# SCH_CustomESP32Board_2024-06-23.net
KiCad netlist of a schematic drawn in EasyEDA
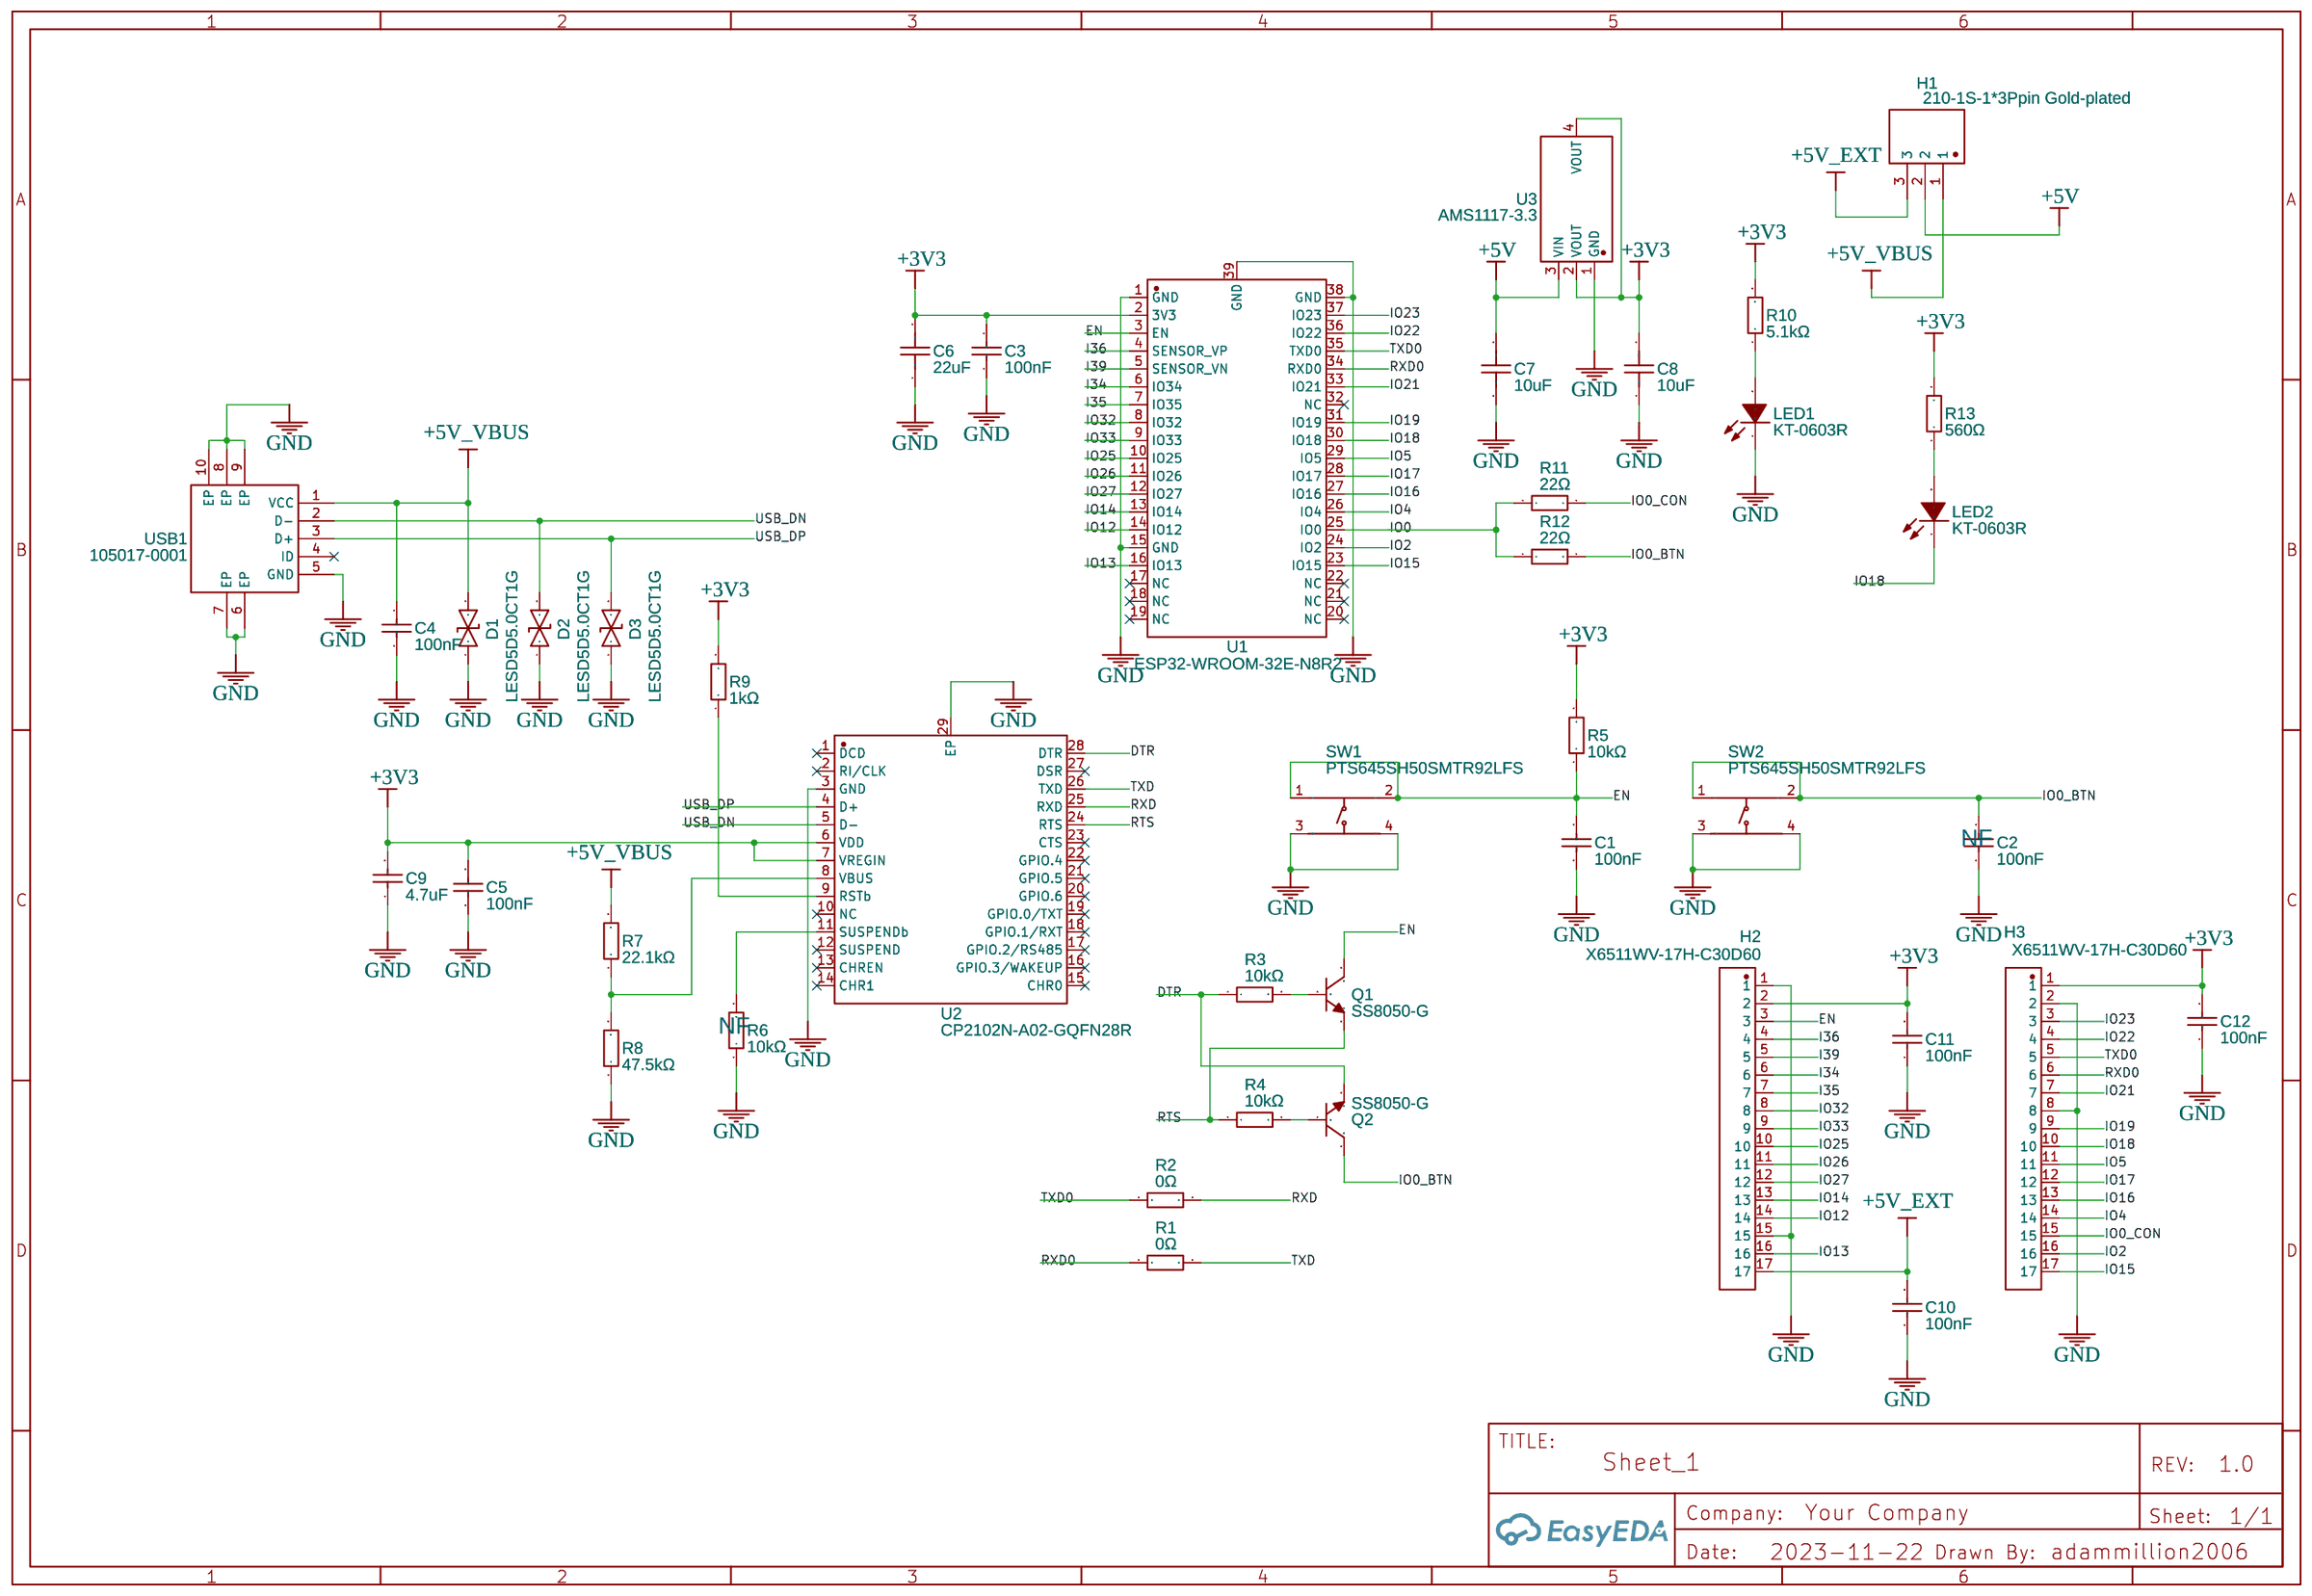
[diagram p0: schematic sheet]

(export (version "E")
  (design (tool "Eeschema 10.0.6"))
  (components
    (comp (ref "C1")
      (value "100nF")
      (fields
        (field (name "Manufacturer Part") "CL05B104KO5NNNC")
        (field (name "Manufacturer") "SAMSUNG(三星)")
      )
      (libsource (lib "") (part "CL05B104KO5NNNC"))
    )
    (comp (ref "C2")
      (value "100nF")
      (fields
        (field (name "Manufacturer Part") "CL05B104KO5NNNC")
        (field (name "Manufacturer") "SAMSUNG(三星)")
      )
      (libsource (lib "") (part "CL05B104KO5NNNC"))
    )
    (comp (ref "C3")
      (value "100nF")
      (fields
        (field (name "Manufacturer Part") "CL05B104KO5NNNC")
        (field (name "Manufacturer") "SAMSUNG(三星)")
      )
      (libsource (lib "") (part "CL05B104KO5NNNC"))
    )
    (comp (ref "C4")
      (value "100nF")
      (fields
        (field (name "Manufacturer Part") "CL05B104KO5NNNC")
        (field (name "Manufacturer") "SAMSUNG(三星)")
      )
      (libsource (lib "") (part "CL05B104KO5NNNC"))
    )
    (comp (ref "C5")
      (value "100nF")
      (fields
        (field (name "Manufacturer Part") "CL05B104KO5NNNC")
        (field (name "Manufacturer") "SAMSUNG(三星)")
      )
      (libsource (lib "") (part "CL05B104KO5NNNC"))
    )
    (comp (ref "C6")
      (value "22uF")
      (fields
        (field (name "Manufacturer Part") "CL21A226MAQNNNE")
        (field (name "Manufacturer") "SAMSUNG(三星)")
      )
      (libsource (lib "") (part "CL21A226MAQNNNE"))
    )
    (comp (ref "C7")
      (value "10uF")
      (fields
        (field (name "Manufacturer Part") "CL10A106KP8NNNC")
        (field (name "Manufacturer") "SAMSUNG(三星)")
      )
      (libsource (lib "") (part "CL10A106KP8NNNC"))
    )
    (comp (ref "C8")
      (value "10uF")
      (fields
        (field (name "Manufacturer Part") "CL10A106KP8NNNC")
        (field (name "Manufacturer") "SAMSUNG(三星)")
      )
      (libsource (lib "") (part "CL10A106KP8NNNC"))
    )
    (comp (ref "C9")
      (value "4.7uF")
      (fields
        (field (name "Manufacturer Part") "CL05A475MP5NRNC")
        (field (name "Manufacturer") "SAMSUNG(三星)")
      )
      (libsource (lib "") (part "CL05A475MP5NRNC"))
    )
    (comp (ref "C10")
      (value "100nF")
      (fields
        (field (name "Manufacturer Part") "CL05B104KO5NNNC")
        (field (name "Manufacturer") "SAMSUNG(三星)")
      )
      (libsource (lib "") (part "CL05B104KO5NNNC"))
    )
    (comp (ref "C11")
      (value "100nF")
      (fields
        (field (name "Manufacturer Part") "CL05B104KO5NNNC")
        (field (name "Manufacturer") "SAMSUNG(三星)")
      )
      (libsource (lib "") (part "CL05B104KO5NNNC"))
    )
    (comp (ref "C12")
      (value "100nF")
      (fields
        (field (name "Manufacturer Part") "CL05B104KO5NNNC")
        (field (name "Manufacturer") "SAMSUNG(三星)")
      )
      (libsource (lib "") (part "CL05B104KO5NNNC"))
    )
    (comp (ref "D1")
      (value "LESD5D5.0CT1G")
      (fields (field (name "Manufacturer") "LRC(乐山无线电)"))
      (libsource (lib "") (part "LESD5D5.0CT1G"))
    )
    (comp (ref "D2")
      (value "LESD5D5.0CT1G")
      (fields (field (name "Manufacturer") "LRC(乐山无线电)"))
      (libsource (lib "") (part "LESD5D5.0CT1G"))
    )
    (comp (ref "D3")
      (value "LESD5D5.0CT1G")
      (fields (field (name "Manufacturer") "LRC(乐山无线电)"))
      (libsource (lib "") (part "LESD5D5.0CT1G"))
    )
    (comp (ref "H1")
      (value "210-1S-1*3Ppin Gold-plated")
      (fields (field (name "Manufacturer Part") "B-2101S03P-A110") (field (name "Manufacturer") "Ckmtw(灿科盟)"))
      (libsource (lib "") (part "210-1S-1*3Ppin Gold-plated"))
    )
    (comp (ref "H2")
      (value "X6511WV-17H-C30D60")
      (fields
        (field (name "Manufacturer Part") "X6511WV-17H-C60D30")
        (field (name "Manufacturer") "XKB Connectivity(中国星坤)")
      )
      (libsource (lib "") (part "X6511WV-17H-C30D60"))
    )
    (comp (ref "H3")
      (value "X6511WV-17H-C30D60")
      (fields
        (field (name "Manufacturer Part") "X6511WV-17H-C60D30")
        (field (name "Manufacturer") "XKB Connectivity(中国星坤)")
      )
      (libsource (lib "") (part "X6511WV-17H-C30D60"))
    )
    (comp (ref "LED1")
      (value "KT-0603R")
      (fields (field (name "Manufacturer") "KENTO"))
      (libsource (lib "") (part "KT-0603R"))
    )
    (comp (ref "LED2")
      (value "KT-0603R")
      (fields (field (name "Manufacturer") "KENTO"))
      (libsource (lib "") (part "KT-0603R"))
    )
    (comp (ref "Q1")
      (value "SS8050-G")
      (fields (field (name "Manufacturer") "CJ(江苏长电/长晶)"))
      (libsource (lib "") (part "SS8050-G_1"))
    )
    (comp (ref "Q2")
      (value "SS8050-G")
      (fields (field (name "Manufacturer") "CJ(江苏长电/长晶)"))
      (libsource (lib "") (part "SS8050-G"))
    )
    (comp (ref "R1")
      (value "0Ω")
      (fields
        (field (name "Manufacturer Part") "0402WGF0000TCE")
        (field (name "Manufacturer") "UNI-ROYAL(厚声)")
      )
      (libsource (lib "") (part "0402WGF0000TCE"))
    )
    (comp (ref "R2")
      (value "0Ω")
      (fields
        (field (name "Manufacturer Part") "0402WGF0000TCE")
        (field (name "Manufacturer") "UNI-ROYAL(厚声)")
      )
      (libsource (lib "") (part "0402WGF0000TCE"))
    )
    (comp (ref "R3")
      (value "10kΩ")
      (fields
        (field (name "Manufacturer Part") "0402WGF1002TCE")
        (field (name "Manufacturer") "UNI-ROYAL(厚声)")
      )
      (libsource (lib "") (part "0402WGF1002TCE_1"))
    )
    (comp (ref "R4")
      (value "10kΩ")
      (fields
        (field (name "Manufacturer Part") "0402WGF1002TCE")
        (field (name "Manufacturer") "UNI-ROYAL(厚声)")
      )
      (libsource (lib "") (part "0402WGF1002TCE_1"))
    )
    (comp (ref "R5")
      (value "10kΩ")
      (fields
        (field (name "Manufacturer Part") "0402WGF1002TCE")
        (field (name "Manufacturer") "UNI-ROYAL(厚声)")
      )
      (libsource (lib "") (part "0402WGF1002TCE"))
    )
    (comp (ref "R6")
      (value "10kΩ")
      (fields
        (field (name "Manufacturer Part") "0402WGF1002TCE")
        (field (name "Manufacturer") "UNI-ROYAL(厚声)")
      )
      (libsource (lib "") (part "0402WGF1002TCE"))
    )
    (comp (ref "R7")
      (value "22.1kΩ")
      (fields
        (field (name "Manufacturer Part") "0402WGF2212TCE")
        (field (name "Manufacturer") "UNI-ROYAL(厚声)")
      )
      (libsource (lib "") (part "0402WGF2212TCE"))
    )
    (comp (ref "R8")
      (value "47.5kΩ")
      (fields
        (field (name "Manufacturer Part") "0402WGF4752TCE")
        (field (name "Manufacturer") "UNI-ROYAL(厚声)")
      )
      (libsource (lib "") (part "0402WGF4752TCE"))
    )
    (comp (ref "R9")
      (value "1kΩ")
      (fields
        (field (name "Manufacturer Part") "0402WGF1001TCE")
        (field (name "Manufacturer") "UNI-ROYAL(厚声)")
      )
      (libsource (lib "") (part "0402WGF1001TCE"))
    )
    (comp (ref "R10")
      (value "5.1kΩ")
      (fields
        (field (name "Manufacturer Part") "0402WGF5101TCE")
        (field (name "Manufacturer") "UNI-ROYAL(厚声)")
      )
      (libsource (lib "") (part "0402WGF5101TCE"))
    )
    (comp (ref "R11")
      (value "22Ω")
      (fields
        (field (name "Manufacturer Part") "0402WGF220JTCE")
        (field (name "Manufacturer") "UNI-ROYAL(厚声)")
      )
      (libsource (lib "") (part "0402WGF220JTCE"))
    )
    (comp (ref "R12")
      (value "22Ω")
      (fields
        (field (name "Manufacturer Part") "0402WGF220JTCE")
        (field (name "Manufacturer") "UNI-ROYAL(厚声)")
      )
      (libsource (lib "") (part "0402WGF220JTCE"))
    )
    (comp (ref "R13")
      (value "560Ω")
      (fields
        (field (name "Manufacturer Part") "0402WGF5600TCE")
        (field (name "Manufacturer") "UNI-ROYAL(厚声)")
      )
      (libsource (lib "") (part "0402WGF5600TCE"))
    )
    (comp (ref "SW1")
      (value "PTS645SH50SMTR92LFS")
      (fields (field (name "Manufacturer") "C&K"))
      (libsource (lib "") (part "PTS645SH50SMTR92LFS"))
    )
    (comp (ref "SW2")
      (value "PTS645SH50SMTR92LFS")
      (fields (field (name "Manufacturer") "C&K"))
      (libsource (lib "") (part "PTS645SH50SMTR92LFS"))
    )
    (comp (ref "U1")
      (value "ESP32-WROOM-32E-N8R2")
      (fields (field (name "Manufacturer") "ESPRESSIF(乐鑫)"))
      (libsource (lib "") (part "ESP32-WROOM-32E-N8R2"))
    )
    (comp (ref "U2")
      (value "CP2102N-A02-GQFN28R")
      (fields (field (name "Manufacturer") "SILICON LABS(芯科)"))
      (libsource (lib "") (part "CP2102N-A02-GQFN28R"))
    )
    (comp (ref "U3")
      (value "AMS1117-3.3")
      (fields (field (name "Manufacturer") "AMS"))
      (libsource (lib "") (part "AMS1117-3.3"))
    )
    (comp (ref "USB1")
      (value "105017-0001")
      (fields (field (name "Manufacturer Part") "1050170001") (field (name "Manufacturer") "MOLEX"))
      (libsource (lib "") (part "105017-0001"))
    )
  )
  (nets
    (net (code "1") (name "+3V3") (class "Default")
      (node (ref "C11") (pin "2") (pinfunction "2_2") (pintype "input"))
      (node (ref "C12") (pin "2") (pinfunction "2_2") (pintype "input"))
      (node (ref "C3") (pin "2") (pinfunction "2_2") (pintype "input"))
      (node (ref "C5") (pin "2") (pinfunction "2_2") (pintype "input"))
      (node (ref "C6") (pin "2") (pinfunction "2_2") (pintype "unspecified"))
      (node (ref "C8") (pin "2") (pinfunction "2_2") (pintype "unspecified"))
      (node (ref "C9") (pin "2") (pinfunction "2_2") (pintype "input"))
      (node (ref "H2") (pin "2") (pinfunction "2_2") (pintype "unspecified"))
      (node (ref "H3") (pin "1") (pinfunction "1_1") (pintype "unspecified"))
      (node (ref "R10") (pin "2") (pinfunction "2_2") (pintype "input"))
      (node (ref "R13") (pin "2") (pinfunction "2_2") (pintype "input"))
      (node (ref "R5") (pin "2") (pinfunction "2_2") (pintype "input"))
      (node (ref "R9") (pin "2") (pinfunction "2_2") (pintype "input"))
      (node (ref "U1") (pin "2") (pinfunction "3V3_2") (pintype "unspecified"))
      (node (ref "U2") (pin "6") (pinfunction "VDD_6") (pintype "unspecified"))
      (node (ref "U2") (pin "7") (pinfunction "VREGIN_7") (pintype "unspecified"))
      (node (ref "U3") (pin "2") (pinfunction "VOUT_2") (pintype "unspecified"))
      (node (ref "U3") (pin "4") (pinfunction "VOUT_4") (pintype "unspecified"))
    )
    (net (code "2") (name "+5V") (class "Default")
      (node (ref "C7") (pin "2") (pinfunction "2_2") (pintype "unspecified"))
      (node (ref "H1") (pin "2") (pinfunction "2_2") (pintype "unspecified"))
      (node (ref "U3") (pin "3") (pinfunction "VIN_3") (pintype "unspecified"))
    )
    (net (code "3") (name "+5V_EXT") (class "Default")
      (node (ref "C10") (pin "2") (pinfunction "2_2") (pintype "input"))
      (node (ref "H1") (pin "3") (pinfunction "3_3") (pintype "unspecified"))
      (node (ref "H2") (pin "17") (pinfunction "17_17") (pintype "unspecified"))
    )
    (net (code "4") (name "+5V_VBUS") (class "Default")
      (node (ref "C4") (pin "2") (pinfunction "2_2") (pintype "input"))
      (node (ref "D1") (pin "2") (pinfunction "2_2") (pintype "unspecified"))
      (node (ref "H1") (pin "1") (pinfunction "1_1") (pintype "unspecified"))
      (node (ref "R7") (pin "2") (pinfunction "2_2") (pintype "input"))
      (node (ref "USB1") (pin "1") (pinfunction "VCC_1") (pintype "unspecified"))
    )
    (net (code "5") (name "/DTR") (class "Default")
      (node (ref "Q2") (pin "2") (pinfunction "E_2") (pintype "input"))
      (node (ref "R3") (pin "1") (pinfunction "1_1") (pintype "input"))
      (node (ref "U2") (pin "28") (pinfunction "DTR_28") (pintype "unspecified"))
    )
    (net (code "6") (name "/EN") (class "Default")
      (node (ref "C1") (pin "2") (pinfunction "2_2") (pintype "input"))
      (node (ref "H2") (pin "3") (pinfunction "3_3") (pintype "unspecified"))
      (node (ref "Q1") (pin "3") (pinfunction "C_3") (pintype "input"))
      (node (ref "R5") (pin "1") (pinfunction "1_1") (pintype "input"))
      (node (ref "SW1") (pin "1") (pinfunction "1_1") (pintype "unspecified"))
      (node (ref "SW1") (pin "2") (pinfunction "2_2") (pintype "unspecified"))
      (node (ref "U1") (pin "3") (pinfunction "EN_3") (pintype "unspecified"))
    )
    (net (code "7") (name "/I34") (class "Default")
      (node (ref "H2") (pin "6") (pinfunction "6_6") (pintype "unspecified"))
      (node (ref "U1") (pin "6") (pinfunction "IO34_6") (pintype "unspecified"))
    )
    (net (code "8") (name "/I35") (class "Default")
      (node (ref "H2") (pin "7") (pinfunction "7_7") (pintype "unspecified"))
      (node (ref "U1") (pin "7") (pinfunction "IO35_7") (pintype "unspecified"))
    )
    (net (code "9") (name "/I36") (class "Default")
      (node (ref "H2") (pin "4") (pinfunction "4_4") (pintype "unspecified"))
      (node (ref "U1") (pin "4") (pinfunction "SENSOR_VP_4") (pintype "unspecified"))
    )
    (net (code "10") (name "/I39") (class "Default")
      (node (ref "H2") (pin "5") (pinfunction "5_5") (pintype "unspecified"))
      (node (ref "U1") (pin "5") (pinfunction "SENSOR_VN_5") (pintype "unspecified"))
    )
    (net (code "11") (name "/IO0") (class "Default")
      (node (ref "R11") (pin "1") (pinfunction "1_1") (pintype "input"))
      (node (ref "R12") (pin "1") (pinfunction "1_1") (pintype "input"))
      (node (ref "U1") (pin "25") (pinfunction "IO0_25") (pintype "unspecified"))
    )
    (net (code "12") (name "/IO0_BTN") (class "Default")
      (node (ref "C2") (pin "2") (pinfunction "2_2") (pintype "input"))
      (node (ref "Q2") (pin "3") (pinfunction "C_3") (pintype "input"))
      (node (ref "R12") (pin "2") (pinfunction "2_2") (pintype "input"))
      (node (ref "SW2") (pin "1") (pinfunction "1_1") (pintype "unspecified"))
      (node (ref "SW2") (pin "2") (pinfunction "2_2") (pintype "unspecified"))
    )
    (net (code "13") (name "/IO0_CON") (class "Default")
      (node (ref "H3") (pin "15") (pinfunction "15_15") (pintype "unspecified"))
      (node (ref "R11") (pin "2") (pinfunction "2_2") (pintype "input"))
    )
    (net (code "14") (name "/IO2") (class "Default")
      (node (ref "H3") (pin "16") (pinfunction "16_16") (pintype "unspecified"))
      (node (ref "U1") (pin "24") (pinfunction "IO2_24") (pintype "unspecified"))
    )
    (net (code "15") (name "/IO4") (class "Default")
      (node (ref "H3") (pin "14") (pinfunction "14_14") (pintype "unspecified"))
      (node (ref "U1") (pin "26") (pinfunction "IO4_26") (pintype "unspecified"))
    )
    (net (code "16") (name "/IO5") (class "Default")
      (node (ref "H3") (pin "11") (pinfunction "11_11") (pintype "unspecified"))
      (node (ref "U1") (pin "29") (pinfunction "IO5_29") (pintype "unspecified"))
    )
    (net (code "17") (name "/IO12") (class "Default")
      (node (ref "H2") (pin "14") (pinfunction "14_14") (pintype "unspecified"))
      (node (ref "U1") (pin "14") (pinfunction "IO12_14") (pintype "unspecified"))
    )
    (net (code "18") (name "/IO13") (class "Default")
      (node (ref "H2") (pin "16") (pinfunction "16_16") (pintype "unspecified"))
      (node (ref "U1") (pin "16") (pinfunction "IO13_16") (pintype "unspecified"))
    )
    (net (code "19") (name "/IO14") (class "Default")
      (node (ref "H2") (pin "13") (pinfunction "13_13") (pintype "unspecified"))
      (node (ref "U1") (pin "13") (pinfunction "IO14_13") (pintype "unspecified"))
    )
    (net (code "20") (name "/IO15") (class "Default")
      (node (ref "H3") (pin "17") (pinfunction "17_17") (pintype "unspecified"))
      (node (ref "U1") (pin "23") (pinfunction "IO15_23") (pintype "unspecified"))
    )
    (net (code "21") (name "/IO16") (class "Default")
      (node (ref "H3") (pin "13") (pinfunction "13_13") (pintype "unspecified"))
      (node (ref "U1") (pin "27") (pinfunction "IO16_27") (pintype "unspecified"))
    )
    (net (code "22") (name "/IO17") (class "Default")
      (node (ref "H3") (pin "12") (pinfunction "12_12") (pintype "unspecified"))
      (node (ref "U1") (pin "28") (pinfunction "IO17_28") (pintype "unspecified"))
    )
    (net (code "23") (name "/IO18") (class "Default")
      (node (ref "H3") (pin "10") (pinfunction "10_10") (pintype "unspecified"))
      (node (ref "LED2") (pin "1") (pinfunction "K_1") (pintype "unspecified"))
      (node (ref "U1") (pin "30") (pinfunction "IO18_30") (pintype "unspecified"))
    )
    (net (code "24") (name "/IO19") (class "Default")
      (node (ref "H3") (pin "9") (pinfunction "9_9") (pintype "unspecified"))
      (node (ref "U1") (pin "31") (pinfunction "IO19_31") (pintype "unspecified"))
    )
    (net (code "25") (name "/IO21") (class "Default")
      (node (ref "H3") (pin "7") (pinfunction "7_7") (pintype "unspecified"))
      (node (ref "U1") (pin "33") (pinfunction "IO21_33") (pintype "unspecified"))
    )
    (net (code "26") (name "/IO22") (class "Default")
      (node (ref "H3") (pin "4") (pinfunction "4_4") (pintype "unspecified"))
      (node (ref "U1") (pin "36") (pinfunction "IO22_36") (pintype "unspecified"))
    )
    (net (code "27") (name "/IO23") (class "Default")
      (node (ref "H3") (pin "3") (pinfunction "3_3") (pintype "unspecified"))
      (node (ref "U1") (pin "37") (pinfunction "IO23_37") (pintype "unspecified"))
    )
    (net (code "28") (name "/IO25") (class "Default")
      (node (ref "H2") (pin "10") (pinfunction "10_10") (pintype "unspecified"))
      (node (ref "U1") (pin "10") (pinfunction "IO25_10") (pintype "unspecified"))
    )
    (net (code "29") (name "/IO26") (class "Default")
      (node (ref "H2") (pin "11") (pinfunction "11_11") (pintype "unspecified"))
      (node (ref "U1") (pin "11") (pinfunction "IO26_11") (pintype "unspecified"))
    )
    (net (code "30") (name "/IO27") (class "Default")
      (node (ref "H2") (pin "12") (pinfunction "12_12") (pintype "unspecified"))
      (node (ref "U1") (pin "12") (pinfunction "IO27_12") (pintype "unspecified"))
    )
    (net (code "31") (name "/IO32") (class "Default")
      (node (ref "H2") (pin "8") (pinfunction "8_8") (pintype "unspecified"))
      (node (ref "U1") (pin "8") (pinfunction "IO32_8") (pintype "unspecified"))
    )
    (net (code "32") (name "/IO33") (class "Default")
      (node (ref "H2") (pin "9") (pinfunction "9_9") (pintype "unspecified"))
      (node (ref "U1") (pin "9") (pinfunction "IO33_9") (pintype "unspecified"))
    )
    (net (code "33") (name "/RTS") (class "Default")
      (node (ref "Q1") (pin "2") (pinfunction "E_2") (pintype "input"))
      (node (ref "R4") (pin "1") (pinfunction "1_1") (pintype "input"))
      (node (ref "U2") (pin "24") (pinfunction "RTS_24") (pintype "unspecified"))
    )
    (net (code "34") (name "/RXD") (class "Default")
      (node (ref "R2") (pin "2") (pinfunction "2_2") (pintype "input"))
      (node (ref "U2") (pin "25") (pinfunction "RXD_25") (pintype "unspecified"))
    )
    (net (code "35") (name "/RXD0") (class "Default")
      (node (ref "H3") (pin "6") (pinfunction "6_6") (pintype "unspecified"))
      (node (ref "R1") (pin "1") (pinfunction "1_1") (pintype "input"))
      (node (ref "U1") (pin "34") (pinfunction "RXD0_34") (pintype "unspecified"))
    )
    (net (code "36") (name "/TXD") (class "Default")
      (node (ref "R1") (pin "2") (pinfunction "2_2") (pintype "input"))
      (node (ref "U2") (pin "26") (pinfunction "TXD_26") (pintype "unspecified"))
    )
    (net (code "37") (name "/TXD0") (class "Default")
      (node (ref "H3") (pin "5") (pinfunction "5_5") (pintype "unspecified"))
      (node (ref "R2") (pin "1") (pinfunction "1_1") (pintype "input"))
      (node (ref "U1") (pin "35") (pinfunction "TXD0_35") (pintype "unspecified"))
    )
    (net (code "38") (name "/USB_DN") (class "Default")
      (node (ref "D2") (pin "2") (pinfunction "2_2") (pintype "unspecified"))
      (node (ref "U2") (pin "5") (pinfunction "D-_5") (pintype "unspecified"))
      (node (ref "USB1") (pin "2") (pinfunction "D-_2") (pintype "unspecified"))
    )
    (net (code "39") (name "/USB_DP") (class "Default")
      (node (ref "D3") (pin "2") (pinfunction "2_2") (pintype "unspecified"))
      (node (ref "U2") (pin "4") (pinfunction "D+_4") (pintype "unspecified"))
      (node (ref "USB1") (pin "3") (pinfunction "D+_3") (pintype "unspecified"))
    )
    (net (code "40") (name "GND") (class "Default")
      (node (ref "C1") (pin "1") (pinfunction "1_1") (pintype "input"))
      (node (ref "C10") (pin "1") (pinfunction "1_1") (pintype "input"))
      (node (ref "C11") (pin "1") (pinfunction "1_1") (pintype "input"))
      (node (ref "C12") (pin "1") (pinfunction "1_1") (pintype "input"))
      (node (ref "C2") (pin "1") (pinfunction "1_1") (pintype "input"))
      (node (ref "C3") (pin "1") (pinfunction "1_1") (pintype "input"))
      (node (ref "C4") (pin "1") (pinfunction "1_1") (pintype "input"))
      (node (ref "C5") (pin "1") (pinfunction "1_1") (pintype "input"))
      (node (ref "C6") (pin "1") (pinfunction "1_1") (pintype "unspecified"))
      (node (ref "C7") (pin "1") (pinfunction "1_1") (pintype "unspecified"))
      (node (ref "C8") (pin "1") (pinfunction "1_1") (pintype "unspecified"))
      (node (ref "C9") (pin "1") (pinfunction "1_1") (pintype "input"))
      (node (ref "D1") (pin "1") (pinfunction "1_1") (pintype "unspecified"))
      (node (ref "D2") (pin "1") (pinfunction "1_1") (pintype "unspecified"))
      (node (ref "D3") (pin "1") (pinfunction "1_1") (pintype "unspecified"))
      (node (ref "H2") (pin "1") (pinfunction "1_1") (pintype "unspecified"))
      (node (ref "H2") (pin "15") (pinfunction "15_15") (pintype "unspecified"))
      (node (ref "H3") (pin "2") (pinfunction "2_2") (pintype "unspecified"))
      (node (ref "H3") (pin "8") (pinfunction "8_8") (pintype "unspecified"))
      (node (ref "LED1") (pin "1") (pinfunction "K_1") (pintype "unspecified"))
      (node (ref "R6") (pin "1") (pinfunction "1_1") (pintype "input"))
      (node (ref "R8") (pin "1") (pinfunction "1_1") (pintype "input"))
      (node (ref "SW1") (pin "3") (pinfunction "3_3") (pintype "unspecified"))
      (node (ref "SW1") (pin "4") (pinfunction "4_4") (pintype "unspecified"))
      (node (ref "SW2") (pin "3") (pinfunction "3_3") (pintype "unspecified"))
      (node (ref "SW2") (pin "4") (pinfunction "4_4") (pintype "unspecified"))
      (node (ref "U1") (pin "1") (pinfunction "GND_1") (pintype "unspecified"))
      (node (ref "U1") (pin "15") (pinfunction "GND_15") (pintype "unspecified"))
      (node (ref "U1") (pin "38") (pinfunction "GND_38") (pintype "unspecified"))
      (node (ref "U1") (pin "39") (pinfunction "GND_39") (pintype "unspecified"))
      (node (ref "U2") (pin "29") (pinfunction "EP_29") (pintype "unspecified"))
      (node (ref "U2") (pin "3") (pinfunction "GND_3") (pintype "unspecified"))
      (node (ref "U3") (pin "1") (pinfunction "GND_1") (pintype "unspecified"))
      (node (ref "USB1") (pin "10") (pinfunction "EP_10") (pintype "unspecified"))
      (node (ref "USB1") (pin "5") (pinfunction "GND_5") (pintype "unspecified"))
      (node (ref "USB1") (pin "6") (pinfunction "EP_6") (pintype "unspecified"))
      (node (ref "USB1") (pin "7") (pinfunction "EP_7") (pintype "unspecified"))
      (node (ref "USB1") (pin "8") (pinfunction "EP_8") (pintype "unspecified"))
      (node (ref "USB1") (pin "9") (pinfunction "EP_9") (pintype "unspecified"))
    )
    (net (code "41") (name "Net-(LED1-A)") (class "Default")
      (node (ref "LED1") (pin "2") (pinfunction "A_2") (pintype "unspecified"))
      (node (ref "R10") (pin "1") (pinfunction "1_1") (pintype "input"))
    )
    (net (code "42") (name "Net-(LED2-A)") (class "Default")
      (node (ref "LED2") (pin "2") (pinfunction "A_2") (pintype "unspecified"))
      (node (ref "R13") (pin "1") (pinfunction "1_1") (pintype "input"))
    )
    (net (code "43") (name "Net-(Q1-B)") (class "Default")
      (node (ref "Q1") (pin "1") (pinfunction "B_1") (pintype "input"))
      (node (ref "R3") (pin "2") (pinfunction "2_2") (pintype "input"))
    )
    (net (code "44") (name "Net-(Q2-B)") (class "Default")
      (node (ref "Q2") (pin "1") (pinfunction "B_1") (pintype "input"))
      (node (ref "R4") (pin "2") (pinfunction "2_2") (pintype "input"))
    )
    (net (code "45") (name "Net-(U2-RSTb)") (class "Default")
      (node (ref "R9") (pin "1") (pinfunction "1_1") (pintype "input"))
      (node (ref "U2") (pin "9") (pinfunction "RSTb_9") (pintype "unspecified"))
    )
    (net (code "46") (name "Net-(U2-SUSPENDb)") (class "Default")
      (node (ref "R6") (pin "2") (pinfunction "2_2") (pintype "input"))
      (node (ref "U2") (pin "11") (pinfunction "SUSPENDb_11") (pintype "unspecified"))
    )
    (net (code "47") (name "Net-(U2-VBUS)") (class "Default")
      (node (ref "R7") (pin "1") (pinfunction "1_1") (pintype "input"))
      (node (ref "R8") (pin "2") (pinfunction "2_2") (pintype "input"))
      (node (ref "U2") (pin "8") (pinfunction "VBUS_8") (pintype "unspecified"))
    )
    (net (code "48") (name "unconnected-(U1-NC-Pad17)") (class "Default")
      (node (ref "U1") (pin "17") (pinfunction "NC_17") (pintype "unspecified+no_connect"))
    )
    (net (code "49") (name "unconnected-(U1-NC-Pad18)") (class "Default")
      (node (ref "U1") (pin "18") (pinfunction "NC_18") (pintype "unspecified+no_connect"))
    )
    (net (code "50") (name "unconnected-(U1-NC-Pad19)") (class "Default")
      (node (ref "U1") (pin "19") (pinfunction "NC_19") (pintype "unspecified+no_connect"))
    )
    (net (code "51") (name "unconnected-(U1-NC-Pad20)") (class "Default")
      (node (ref "U1") (pin "20") (pinfunction "NC_20") (pintype "unspecified+no_connect"))
    )
    (net (code "52") (name "unconnected-(U1-NC-Pad21)") (class "Default")
      (node (ref "U1") (pin "21") (pinfunction "NC_21") (pintype "unspecified+no_connect"))
    )
    (net (code "53") (name "unconnected-(U1-NC-Pad22)") (class "Default")
      (node (ref "U1") (pin "22") (pinfunction "NC_22") (pintype "unspecified+no_connect"))
    )
    (net (code "54") (name "unconnected-(U1-NC-Pad32)") (class "Default")
      (node (ref "U1") (pin "32") (pinfunction "NC_32") (pintype "unspecified+no_connect"))
    )
    (net (code "55") (name "unconnected-(U2-CHR0-Pad15)") (class "Default")
      (node (ref "U2") (pin "15") (pinfunction "CHR0_15") (pintype "unspecified+no_connect"))
    )
    (net (code "56") (name "unconnected-(U2-CHR1-Pad14)") (class "Default")
      (node (ref "U2") (pin "14") (pinfunction "CHR1_14") (pintype "unspecified+no_connect"))
    )
    (net (code "57") (name "unconnected-(U2-CHREN-Pad13)") (class "Default")
      (node (ref "U2") (pin "13") (pinfunction "CHREN_13") (pintype "unspecified+no_connect"))
    )
    (net (code "58") (name "unconnected-(U2-CTS-Pad23)") (class "Default")
      (node (ref "U2") (pin "23") (pinfunction "CTS_23") (pintype "unspecified+no_connect"))
    )
    (net (code "59") (name "unconnected-(U2-DCD-Pad1)") (class "Default")
      (node (ref "U2") (pin "1") (pinfunction "DCD_1") (pintype "unspecified+no_connect"))
    )
    (net (code "60") (name "unconnected-(U2-DSR-Pad27)") (class "Default")
      (node (ref "U2") (pin "27") (pinfunction "DSR_27") (pintype "unspecified+no_connect"))
    )
    (net (code "61") (name "unconnected-(U2-GPIO.0{slash}TXT-Pad19)") (class "Default")
      (node (ref "U2") (pin "19") (pinfunction "GPIO.0/TXT_19") (pintype "unspecified+no_connect"))
    )
    (net (code "62") (name "unconnected-(U2-GPIO.1{slash}RXT-Pad18)") (class "Default")
      (node (ref "U2") (pin "18") (pinfunction "GPIO.1/RXT_18") (pintype "unspecified+no_connect"))
    )
    (net (code "63") (name "unconnected-(U2-GPIO.2{slash}RS485-Pad17)") (class "Default")
      (node (ref "U2") (pin "17") (pinfunction "GPIO.2/RS485_17") (pintype "unspecified+no_connect"))
    )
    (net (code "64") (name "unconnected-(U2-GPIO.3{slash}WAKEUP-Pad16)") (class "Default")
      (node (ref "U2") (pin "16") (pinfunction "GPIO.3/WAKEUP_16") (pintype "unspecified+no_connect"))
    )
    (net (code "65") (name "unconnected-(U2-GPIO.4-Pad22)") (class "Default")
      (node (ref "U2") (pin "22") (pinfunction "GPIO.4_22") (pintype "unspecified+no_connect"))
    )
    (net (code "66") (name "unconnected-(U2-GPIO.5-Pad21)") (class "Default")
      (node (ref "U2") (pin "21") (pinfunction "GPIO.5_21") (pintype "unspecified+no_connect"))
    )
    (net (code "67") (name "unconnected-(U2-GPIO.6-Pad20)") (class "Default")
      (node (ref "U2") (pin "20") (pinfunction "GPIO.6_20") (pintype "unspecified+no_connect"))
    )
    (net (code "68") (name "unconnected-(U2-NC-Pad10)") (class "Default")
      (node (ref "U2") (pin "10") (pinfunction "NC_10") (pintype "unspecified+no_connect"))
    )
    (net (code "69") (name "unconnected-(U2-RI{slash}CLK-Pad2)") (class "Default")
      (node (ref "U2") (pin "2") (pinfunction "RI/CLK_2") (pintype "unspecified+no_connect"))
    )
    (net (code "70") (name "unconnected-(U2-SUSPEND-Pad12)") (class "Default")
      (node (ref "U2") (pin "12") (pinfunction "SUSPEND_12") (pintype "unspecified+no_connect"))
    )
    (net (code "71") (name "unconnected-(USB1-ID-Pad4)") (class "Default")
      (node (ref "USB1") (pin "4") (pinfunction "ID_4") (pintype "unspecified+no_connect"))
    )
  )
)
